# misc_B.net
KiCad netlist of a schematic drawn in Altium Designer
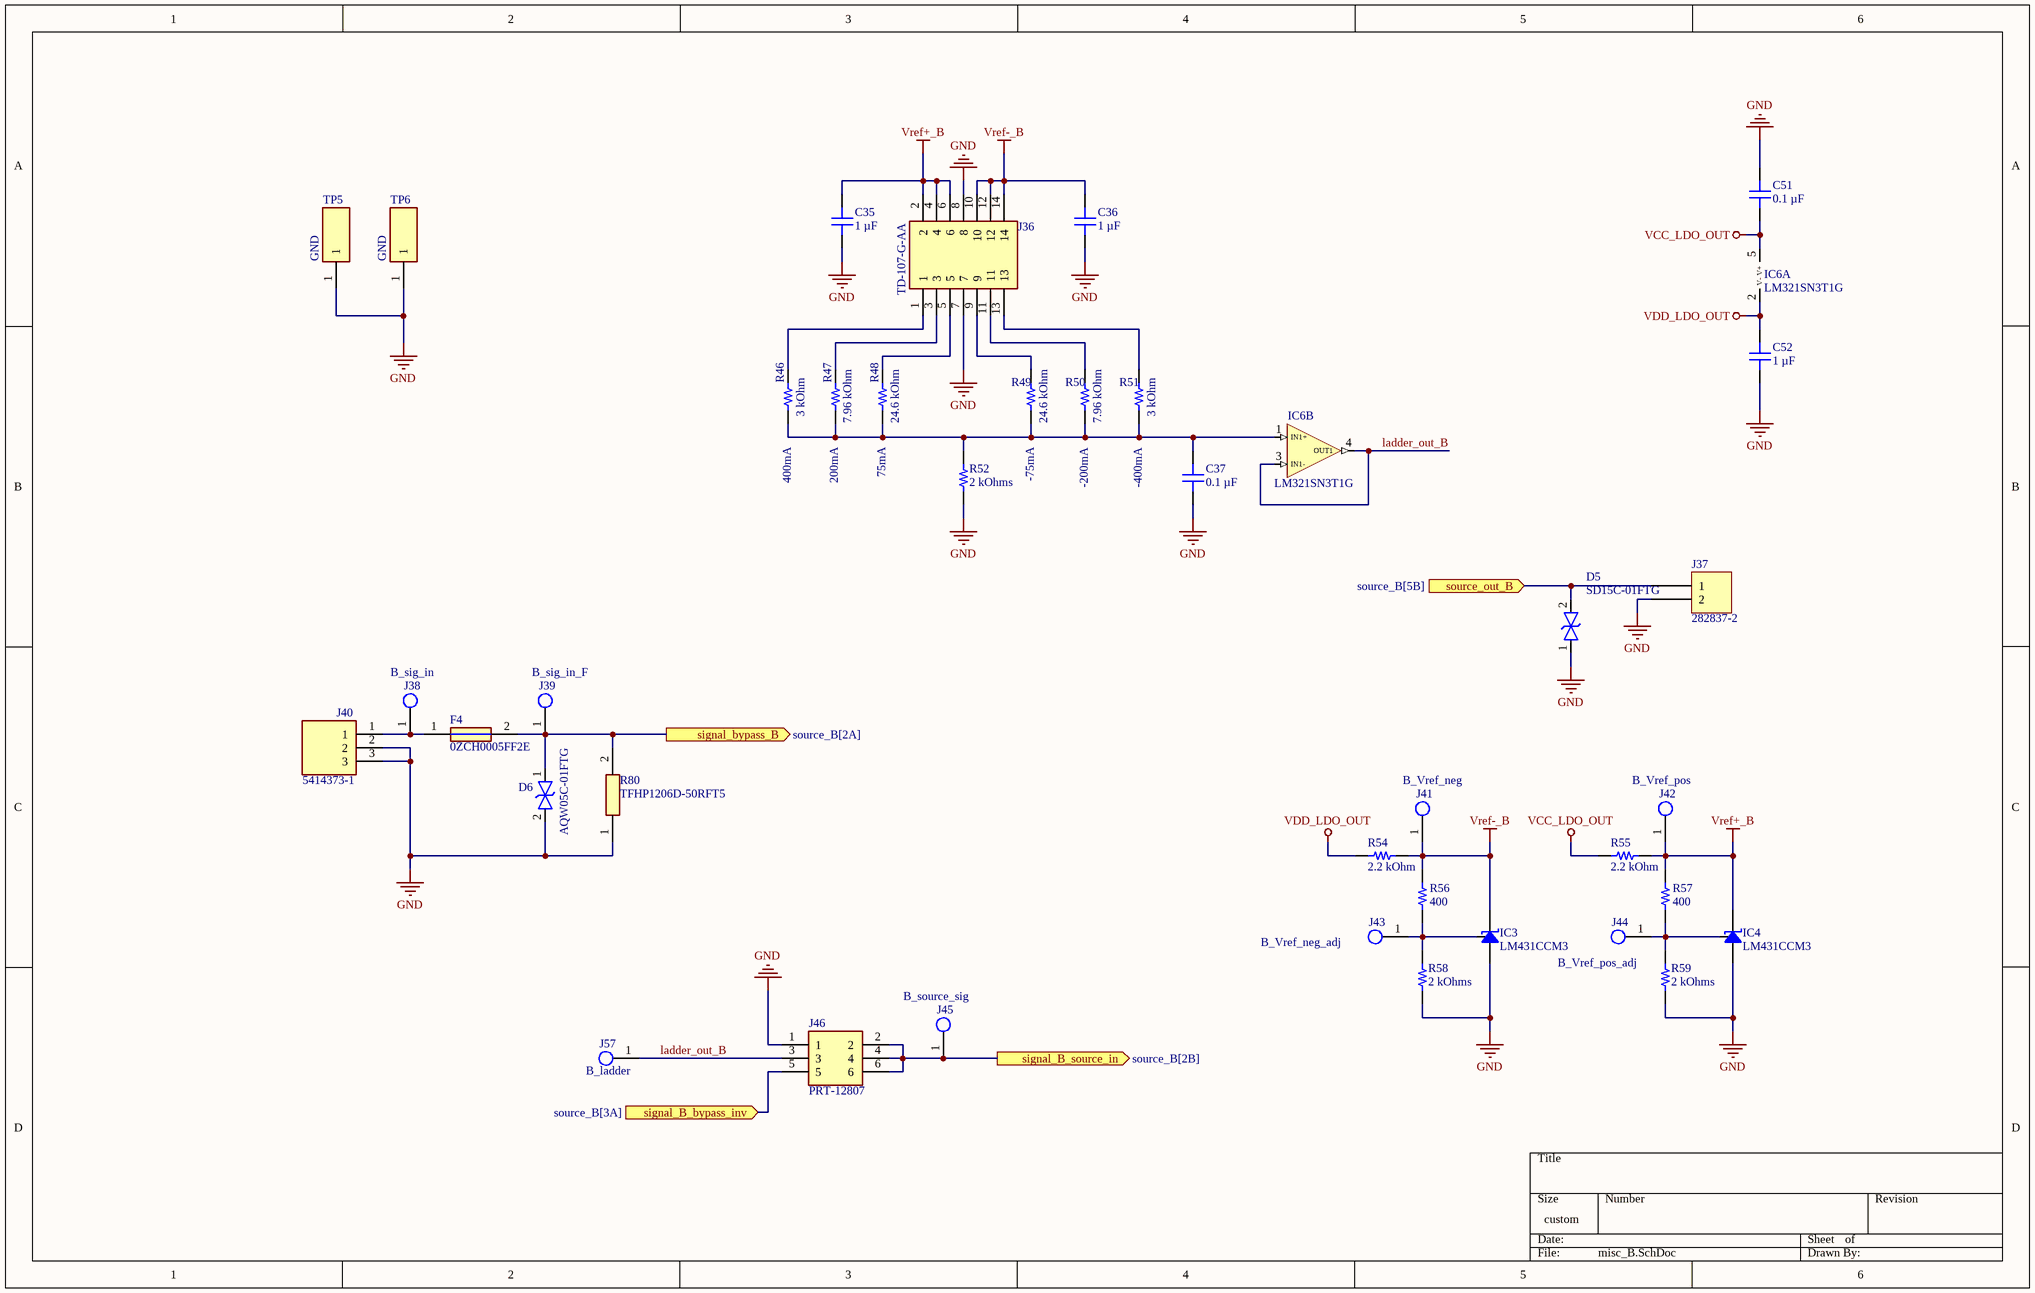
[diagram p0: misc_B.SchDoc]

(export (version "E")
  (design (tool "Eeschema 10.0.6"))
  (components
    (comp (ref "C35")
      (value "1 µF")
      (footprint "CAP 1206_3216 - 0.8MM")
      (description "CAP CER 1UF 50V X7R 1206")
      (fields
        (field (name "PART NUMBER") "885012208093")
        (field (name "CAPACITANCE") "1 µF")
        (field (name "MANUFACTURER") "Würth Elektronik")
      )
      (libsource (lib "Celestial Altium Library - altium_library") (part "Capacitor"))
    )
    (comp (ref "C36")
      (value "1 µF")
      (footprint "CAP 1206_3216 - 0.8MM")
      (description "CAP CER 1UF 50V X7R 1206")
      (fields
        (field (name "PART NUMBER") "885012208093")
        (field (name "CAPACITANCE") "1 µF")
        (field (name "MANUFACTURER") "Würth Elektronik")
      )
      (libsource (lib "Celestial Altium Library - altium_library") (part "Capacitor"))
    )
    (comp (ref "C37")
      (value "0.1 µF")
      (footprint "CAP 1206_3216 - 0.8MM")
      (description "CAP CER 0.1UF 50V X7R 1206")
      (fields
        (field (name "PART NUMBER") "885012208087")
        (field (name "CAPACITANCE") "0.1 µF")
        (field (name "MANUFACTURER") "Würth Elektronik")
      )
      (libsource (lib "Celestial Altium Library - altium_library") (part "Capacitor"))
    )
    (comp (ref "C51")
      (value "0.1 µF")
      (footprint "CAP 1206_3216 - 0.8MM")
      (description "CAP CER 0.1UF 50V X7R 1206")
      (fields
        (field (name "PART NUMBER") "885012208087")
        (field (name "CAPACITANCE") "0.1 µF")
        (field (name "MANUFACTURER") "Würth Elektronik")
      )
      (libsource (lib "Celestial Altium Library - altium_library") (part "Capacitor"))
    )
    (comp (ref "C52")
      (value "1 µF")
      (footprint "CAP 1206_3216 - 0.8MM")
      (description "CAP CER 1UF 50V X7R 1206")
      (fields
        (field (name "PART NUMBER") "885012208093")
        (field (name "CAPACITANCE") "1 µF")
        (field (name "MANUFACTURER") "Würth Elektronik")
      )
      (libsource (lib "Celestial Altium Library - altium_library") (part "Capacitor"))
    )
    (comp (ref "D5")
      (value "SD15C-01FTG")
      (footprint "za_koncar:SD15C01FTG")
      (description "TVS Diode (Bi-directional)")
      (fields (field (name "MOUSER PART NUMBER") "576-SD15C-01FTG"))
      (libsource (lib "za_koncar") (part "SD15C-01FTG"))
    )
    (comp (ref "D6")
      (value "AQW05C-01FTG")
      (footprint "SOD2613X100N")
      (description "TVS Diode (Bi-directional)")
      (fields (field (name "MOUSER PART NUMBER") "576-AQW05C-01FTG"))
      (libsource (lib "za_koncar") (part "AQW05C-01FTG"))
    )
    (comp (ref "F4")
      (value "0ZCH0005FF2E")
      (footprint "FUSC3226X115N")
      (description "Fuse")
      (fields (field (name "MOUSER PART NUMBER") "530-0ZCH0005FF2E"))
      (libsource (lib "za_koncar") (part "0ZCH0005FF2E"))
    )
    (comp (ref "IC3")
      (value "LM431CCM3")
      (footprint "SOT96P240X110-3N")
      (description "Integrated Circuit")
      (fields
        (field (name "MANUFACTURER_PART_NUMBER") "LM431CCM3/NOPB")
        (field (name "MOUSER PART NUMBER") "926-LM431CCM3/NOPB")
      )
      (libsource (lib "za_koncar") (part "LM431CCM3/NOPB"))
    )
    (comp (ref "IC4")
      (value "LM431CCM3")
      (footprint "SOT96P240X110-3N")
      (description "Integrated Circuit")
      (fields
        (field (name "MANUFACTURER_PART_NUMBER") "LM431CCM3/NOPB")
        (field (name "MOUSER PART NUMBER") "926-LM431CCM3/NOPB")
      )
      (libsource (lib "za_koncar") (part "LM431CCM3/NOPB"))
    )
    (comp (ref "IC6")
      (value "LM321SN3T1G")
      (footprint "za_koncar:SOT95P275X110-5N")
      (description "Integrated Circuit")
      (fields (field (name "MOUSER PART NUMBER") "863-LM321SN3T1G"))
      (libsource (lib "za_koncar") (part "LM321SN3T1G"))
    )
    (comp (ref "J36")
      (value "TD-107-G-AA")
      (footprint "HDRV14W46P254_2X7_1778X508X818P")
      (description "Connector")
      (fields (field (name "MOUSER PART NUMBER") "200-TD107GAA"))
      (libsource (lib "za_koncar") (part "TD-107-G-AA"))
    )
    (comp (ref "J37")
      (value "282837-2")
      (footprint "TE 282837-2")
      (description "TERM BLK 2P SIDE ENT 5.08MM PCB")
      (fields (field (name "MANUFACTURER") "TE Connectivity AMP Connectors") (field (name "VOLTAGE") "300 V"))
      (libsource (lib "Celestial Altium Library - altium_library") (part "2 Pin"))
    )
    (comp (ref "J38")
      (value "B_sig_in")
      (footprint "FP-5001-MFG")
      (description "PC TEST POINT MINIATURE BLACK")
      (libsource (lib "za_koncar") (part "5001"))
    )
    (comp (ref "J39")
      (value "B_sig_in_F")
      (footprint "FP-5001-MFG")
      (description "PC TEST POINT MINIATURE BLACK")
      (libsource (lib "za_koncar") (part "5001"))
    )
    (comp (ref "J40")
      (value "5414373-1")
      (footprint "za_koncar:54143731")
      (description "Connector")
      (fields (field (name "MOUSER PART NUMBER") "571-5414373-1"))
      (libsource (lib "za_koncar") (part "5414373-1"))
    )
    (comp (ref "J41")
      (value "B_Vref_neg")
      (footprint "FP-5001-MFG")
      (description "PC TEST POINT MINIATURE BLACK")
      (libsource (lib "za_koncar") (part "5001"))
    )
    (comp (ref "J42")
      (value "B_Vref_pos")
      (footprint "FP-5001-MFG")
      (description "PC TEST POINT MINIATURE BLACK")
      (libsource (lib "za_koncar") (part "5001"))
    )
    (comp (ref "J43")
      (value "B_Vref_neg_adj")
      (footprint "FP-5001-MFG")
      (description "PC TEST POINT MINIATURE BLACK")
      (libsource (lib "za_koncar") (part "5001"))
    )
    (comp (ref "J44")
      (value "B_Vref_pos_adj")
      (footprint "FP-5001-MFG")
      (description "PC TEST POINT MINIATURE BLACK")
      (libsource (lib "za_koncar") (part "5001"))
    )
    (comp (ref "J45")
      (value "B_source_sig")
      (footprint "FP-5001-MFG")
      (description "PC TEST POINT MINIATURE BLACK")
      (libsource (lib "za_koncar") (part "5001"))
    )
    (comp (ref "J46")
      (value "PRT-12807")
      (footprint "HDRV6W82P254_2X3_762X500X884P")
      (description "Connector")
      (fields (field (name "MOUSER PART NUMBER") "474-PRT-12807"))
      (libsource (lib "za_koncar") (part "PRT-12807"))
    )
    (comp (ref "J57")
      (value "B_ladder")
      (footprint "FP-5001-MFG")
      (description "PC TEST POINT MINIATURE BLACK")
      (libsource (lib "za_koncar") (part "5001"))
    )
    (comp (ref "R46")
      (value "3 kOhm")
      (footprint "za_koncar:ERA3AEB101V")
      (description "Resistor")
      (fields
        (field (name "MANUFACTURER_PART_NUMBER") "ERA-3AEB302V")
        (field (name "MOUSER PART NUMBER") "667-ERA-3AEB302V")
      )
      (libsource (lib "za_koncar") (part "ERA-3AEB302V"))
    )
    (comp (ref "R47")
      (value "7.96 kOhm")
      (footprint "za_koncar:ERA3AEB101V")
      (description "Resistor")
      (fields
        (field (name "MANUFACTURER_PART_NUMBER") "ERA-3AEB302V")
        (field (name "MOUSER PART NUMBER") "667-ERA-3AEB302V")
      )
      (libsource (lib "za_koncar") (part "TNPW06037K96BEEA"))
    )
    (comp (ref "R48")
      (value "24.6 kOhm")
      (footprint "za_koncar:ERA3AEB101V")
      (description "Resistor")
      (fields
        (field (name "MANUFACTURER_PART_NUMBER") "ERA-3AEB302V")
        (field (name "MOUSER PART NUMBER") "667-ERA-3AEB302V")
      )
      (libsource (lib "za_koncar") (part "RT0603BRD0724K6L"))
    )
    (comp (ref "R49")
      (value "24.6 kOhm")
      (footprint "za_koncar:ERA3AEB101V")
      (description "Resistor")
      (fields
        (field (name "MANUFACTURER_PART_NUMBER") "ERA-3AEB302V")
        (field (name "MOUSER PART NUMBER") "667-ERA-3AEB302V")
      )
      (libsource (lib "za_koncar") (part "RT0603BRD0724K6L"))
    )
    (comp (ref "R50")
      (value "7.96 kOhm")
      (footprint "za_koncar:ERA3AEB101V")
      (description "Resistor")
      (fields
        (field (name "MANUFACTURER_PART_NUMBER") "ERA-3AEB302V")
        (field (name "MOUSER PART NUMBER") "667-ERA-3AEB302V")
      )
      (libsource (lib "za_koncar") (part "TNPW06037K96BEEA"))
    )
    (comp (ref "R51")
      (value "3 kOhm")
      (footprint "za_koncar:ERA3AEB101V")
      (description "Resistor")
      (fields
        (field (name "MANUFACTURER_PART_NUMBER") "ERA-3AEB302V")
        (field (name "MOUSER PART NUMBER") "667-ERA-3AEB302V")
      )
      (libsource (lib "za_koncar") (part "ERA-3AEB302V"))
    )
    (comp (ref "R52")
      (value "2 kOhms")
      (footprint "RES 1206_3216")
      (description "RES SMD 2K OHM 0.1% 1/4W 1206")
      (fields
        (field (name "PART NUMBER") "ERA-8AEB202V")
        (field (name "MANUFACTURER") "Panasonic Electronic Components")
      )
      (libsource (lib "Celestial Altium Library - altium_library") (part "Resistor"))
    )
    (comp (ref "R54")
      (value "2.2 kOhm")
      (footprint "za_koncar:RESC3116X65N")
      (description "Resistor")
      (fields
        (field (name "MANUFACTURER_PART_NUMBER") "RT1206FRE072K2L")
        (field (name "MOUSER PART NUMBER") "603-RT1206FRE072K2L")
      )
      (libsource (lib "za_koncar") (part "RT1206FRE072K2L"))
    )
    (comp (ref "R55")
      (value "2.2 kOhm")
      (footprint "za_koncar:RESC3116X65N")
      (description "Resistor")
      (fields
        (field (name "MANUFACTURER_PART_NUMBER") "RT1206FRE072K2L")
        (field (name "MOUSER PART NUMBER") "603-RT1206FRE072K2L")
      )
      (libsource (lib "za_koncar") (part "RT1206FRE072K2L"))
    )
    (comp (ref "R56")
      (value "400")
      (footprint "RESC3116X65N")
      (description "Resistor")
      (fields
        (field (name "MANUFACTURER_PART_NUMBER") "RT1206BRD07400RL")
        (field (name "MOUSER PART NUMBER") "603-RT1206BRD07400RL")
      )
      (libsource (lib "za_koncar") (part "RT1206BRD07400RL"))
    )
    (comp (ref "R57")
      (value "400")
      (footprint "RESC3116X65N")
      (description "Resistor")
      (fields
        (field (name "MANUFACTURER_PART_NUMBER") "RT1206BRD07400RL")
        (field (name "MOUSER PART NUMBER") "603-RT1206BRD07400RL")
      )
      (libsource (lib "za_koncar") (part "RT1206BRD07400RL"))
    )
    (comp (ref "R58")
      (value "2 kOhms")
      (footprint "RES 1206_3216")
      (description "RES SMD 2K OHM 0.1% 1/4W 1206")
      (fields
        (field (name "PART NUMBER") "ERA-8AEB202V")
        (field (name "MANUFACTURER") "Panasonic Electronic Components")
      )
      (libsource (lib "Celestial Altium Library - altium_library") (part "Resistor"))
    )
    (comp (ref "R59")
      (value "2 kOhms")
      (footprint "RES 1206_3216")
      (description "RES SMD 2K OHM 0.1% 1/4W 1206")
      (fields
        (field (name "PART NUMBER") "ERA-8AEB202V")
        (field (name "MANUFACTURER") "Panasonic Electronic Components")
      )
      (libsource (lib "Celestial Altium Library - altium_library") (part "Resistor"))
    )
    (comp (ref "R80")
      (value "TFHP1206D-50RFT5")
      (footprint "RESC3016X58N")
      (description "Resistor")
      (fields (field (name "MOUSER PART NUMBER") "756-TFHP1206B-50RFT5"))
      (libsource (lib "za_koncar") (part "TFHP1206D-50RFT5"))
    )
    (comp (ref "TP5")
      (value "GND")
      (footprint "za_koncar:S175146R")
      (description "Test Point")
      (fields
        (field (name "MANUFACTURER_PART_NUMBER") "S1751-46R")
        (field (name "MOUSER PART NUMBER") "855-S1751-46R")
      )
      (libsource (lib "za_koncar") (part "S1751-46R"))
    )
    (comp (ref "TP6")
      (value "GND")
      (footprint "za_koncar:S175146R")
      (description "Test Point")
      (fields
        (field (name "MANUFACTURER_PART_NUMBER") "S1751-46R")
        (field (name "MOUSER PART NUMBER") "855-S1751-46R")
      )
      (libsource (lib "za_koncar") (part "S1751-46R"))
    )
  )
  (nets
    (net (code "1") (name "/ladder_out_B") (class "Default")
      (node (ref "IC6") (pin "3") (pinfunction "IN1-_3") (pintype "input"))
      (node (ref "IC6") (pin "4") (pinfunction "OUT1_4") (pintype "output"))
      (node (ref "J46") (pin "3") (pinfunction "3_3") (pintype "passive"))
      (node (ref "J57") (pin "1") (pinfunction "1_1") (pintype "passive"))
    )
    (net (code "2") (name "/signal_B_bypass_inv") (class "Default")
      (node (ref "J46") (pin "5") (pinfunction "5_5") (pintype "passive"))
    )
    (net (code "3") (name "/signal_B_source_in") (class "Default")
      (node (ref "J45") (pin "1") (pinfunction "1_1") (pintype "passive"))
      (node (ref "J46") (pin "2") (pinfunction "2_2") (pintype "passive"))
      (node (ref "J46") (pin "4") (pinfunction "4_4") (pintype "passive"))
      (node (ref "J46") (pin "6") (pinfunction "6_6") (pintype "passive"))
    )
    (net (code "4") (name "/signal_bypass_B") (class "Default")
      (node (ref "D6") (pin "1") (pinfunction "1_1") (pintype "passive"))
      (node (ref "F4") (pin "2") (pinfunction "2_2") (pintype "passive"))
      (node (ref "J39") (pin "1") (pinfunction "1_1") (pintype "passive"))
      (node (ref "R80") (pin "2") (pinfunction "2_2") (pintype "passive"))
    )
    (net (code "5") (name "/source_out_B") (class "Default")
      (node (ref "D5") (pin "2") (pinfunction "2_2") (pintype "passive"))
      (node (ref "J37") (pin "1") (pinfunction "1_1") (pintype "passive"))
    )
    (net (code "6") (name "GND") (class "Default")
      (node (ref "C35") (pin "2") (pinfunction "2_2") (pintype "passive"))
      (node (ref "C36") (pin "1") (pinfunction "1_1") (pintype "passive"))
      (node (ref "C37") (pin "2") (pinfunction "2_2") (pintype "passive"))
      (node (ref "C51") (pin "1") (pinfunction "1_1") (pintype "passive"))
      (node (ref "C52") (pin "2") (pinfunction "2_2") (pintype "passive"))
      (node (ref "D5") (pin "1") (pinfunction "1_1") (pintype "passive"))
      (node (ref "D6") (pin "2") (pinfunction "2_2") (pintype "passive"))
      (node (ref "IC3") (pin "2") (pinfunction "Anode_2") (pintype "passive"))
      (node (ref "IC4") (pin "2") (pinfunction "Anode_2") (pintype "passive"))
      (node (ref "J36") (pin "7") (pinfunction "7_7") (pintype "passive"))
      (node (ref "J36") (pin "8") (pinfunction "8_8") (pintype "passive"))
      (node (ref "J37") (pin "2") (pinfunction "2_2") (pintype "passive"))
      (node (ref "J40") (pin "2") (pinfunction "2_2") (pintype "passive"))
      (node (ref "J40") (pin "3") (pinfunction "3_3") (pintype "passive"))
      (node (ref "J46") (pin "1") (pinfunction "1_1") (pintype "passive"))
      (node (ref "R52") (pin "1") (pinfunction "1_1") (pintype "passive"))
      (node (ref "R58") (pin "1") (pinfunction "1_1") (pintype "passive"))
      (node (ref "R59") (pin "1") (pinfunction "1_1") (pintype "passive"))
      (node (ref "R80") (pin "1") (pinfunction "1_1") (pintype "passive"))
      (node (ref "TP5") (pin "1") (pinfunction "1_1") (pintype "passive"))
      (node (ref "TP6") (pin "1") (pinfunction "1_1") (pintype "passive"))
    )
    (net (code "7") (name "Net-(F4-Pad1)") (class "Default")
      (node (ref "F4") (pin "1") (pinfunction "1_1") (pintype "passive"))
      (node (ref "J38") (pin "1") (pinfunction "1_1") (pintype "passive"))
      (node (ref "J40") (pin "1") (pinfunction "1_1") (pintype "passive"))
    )
    (net (code "8") (name "Net-(IC3-Ref)") (class "Default")
      (node (ref "IC3") (pin "3") (pinfunction "Ref_3") (pintype "passive"))
      (node (ref "J43") (pin "1") (pinfunction "1_1") (pintype "passive"))
      (node (ref "R56") (pin "1") (pinfunction "1_1") (pintype "passive"))
      (node (ref "R58") (pin "2") (pinfunction "2_2") (pintype "passive"))
    )
    (net (code "9") (name "Net-(IC4-Ref)") (class "Default")
      (node (ref "IC4") (pin "3") (pinfunction "Ref_3") (pintype "passive"))
      (node (ref "J44") (pin "1") (pinfunction "1_1") (pintype "passive"))
      (node (ref "R57") (pin "1") (pinfunction "1_1") (pintype "passive"))
      (node (ref "R59") (pin "2") (pinfunction "2_2") (pintype "passive"))
    )
    (net (code "10") (name "Net-(IC6B-IN1+)") (class "Default")
      (node (ref "C37") (pin "1") (pinfunction "1_1") (pintype "passive"))
      (node (ref "IC6") (pin "1") (pinfunction "IN1+_1") (pintype "input"))
      (node (ref "R46") (pin "1") (pinfunction "1_1") (pintype "passive"))
      (node (ref "R47") (pin "1") (pinfunction "1_1") (pintype "passive"))
      (node (ref "R48") (pin "1") (pinfunction "1_1") (pintype "passive"))
      (node (ref "R49") (pin "1") (pinfunction "1_1") (pintype "passive"))
      (node (ref "R50") (pin "1") (pinfunction "1_1") (pintype "passive"))
      (node (ref "R51") (pin "1") (pinfunction "1_1") (pintype "passive"))
      (node (ref "R52") (pin "2") (pinfunction "2_2") (pintype "passive"))
    )
    (net (code "11") (name "Net-(J36-Pad1)") (class "Default")
      (node (ref "J36") (pin "1") (pinfunction "1_1") (pintype "passive"))
      (node (ref "R46") (pin "2") (pinfunction "2_2") (pintype "passive"))
    )
    (net (code "12") (name "Net-(J36-Pad3)") (class "Default")
      (node (ref "J36") (pin "3") (pinfunction "3_3") (pintype "passive"))
      (node (ref "R47") (pin "2") (pinfunction "2_2") (pintype "passive"))
    )
    (net (code "13") (name "Net-(J36-Pad5)") (class "Default")
      (node (ref "J36") (pin "5") (pinfunction "5_5") (pintype "passive"))
      (node (ref "R48") (pin "2") (pinfunction "2_2") (pintype "passive"))
    )
    (net (code "14") (name "Net-(J36-Pad9)") (class "Default")
      (node (ref "J36") (pin "9") (pinfunction "9_9") (pintype "passive"))
      (node (ref "R49") (pin "2") (pinfunction "2_2") (pintype "passive"))
    )
    (net (code "15") (name "Net-(J36-Pad11)") (class "Default")
      (node (ref "J36") (pin "11") (pinfunction "11_11") (pintype "passive"))
      (node (ref "R50") (pin "2") (pinfunction "2_2") (pintype "passive"))
    )
    (net (code "16") (name "Net-(J36-Pad13)") (class "Default")
      (node (ref "J36") (pin "13") (pinfunction "13_13") (pintype "passive"))
      (node (ref "R51") (pin "2") (pinfunction "2_2") (pintype "passive"))
    )
    (net (code "17") (name "VCC_LDO_OUT") (class "Default")
      (node (ref "C51") (pin "2") (pinfunction "2_2") (pintype "passive"))
      (node (ref "IC6") (pin "5") (pinfunction "V+_5") (pintype "power_in"))
      (node (ref "R55") (pin "2") (pinfunction "2_2") (pintype "passive"))
    )
    (net (code "18") (name "VDD_LDO_OUT") (class "Default")
      (node (ref "C52") (pin "1") (pinfunction "1_1") (pintype "passive"))
      (node (ref "IC6") (pin "2") (pinfunction "V-_2") (pintype "power_in"))
      (node (ref "R54") (pin "2") (pinfunction "2_2") (pintype "passive"))
    )
    (net (code "19") (name "Vref+_B") (class "Default")
      (node (ref "C35") (pin "1") (pinfunction "1_1") (pintype "passive"))
      (node (ref "IC4") (pin "1") (pinfunction "Cathode_1") (pintype "passive"))
      (node (ref "J36") (pin "2") (pinfunction "2_2") (pintype "passive"))
      (node (ref "J36") (pin "4") (pinfunction "4_4") (pintype "passive"))
      (node (ref "J36") (pin "6") (pinfunction "6_6") (pintype "passive"))
      (node (ref "J42") (pin "1") (pinfunction "1_1") (pintype "passive"))
      (node (ref "R55") (pin "1") (pinfunction "1_1") (pintype "passive"))
      (node (ref "R57") (pin "2") (pinfunction "2_2") (pintype "passive"))
    )
    (net (code "20") (name "Vref-_B") (class "Default")
      (node (ref "C36") (pin "2") (pinfunction "2_2") (pintype "passive"))
      (node (ref "IC3") (pin "1") (pinfunction "Cathode_1") (pintype "passive"))
      (node (ref "J36") (pin "10") (pinfunction "10_10") (pintype "passive"))
      (node (ref "J36") (pin "12") (pinfunction "12_12") (pintype "passive"))
      (node (ref "J36") (pin "14") (pinfunction "14_14") (pintype "passive"))
      (node (ref "J41") (pin "1") (pinfunction "1_1") (pintype "passive"))
      (node (ref "R54") (pin "1") (pinfunction "1_1") (pintype "passive"))
      (node (ref "R56") (pin "2") (pinfunction "2_2") (pintype "passive"))
    )
  )
)
